# vusb.net
KiCad netlist of a schematic drawn in EAGLE
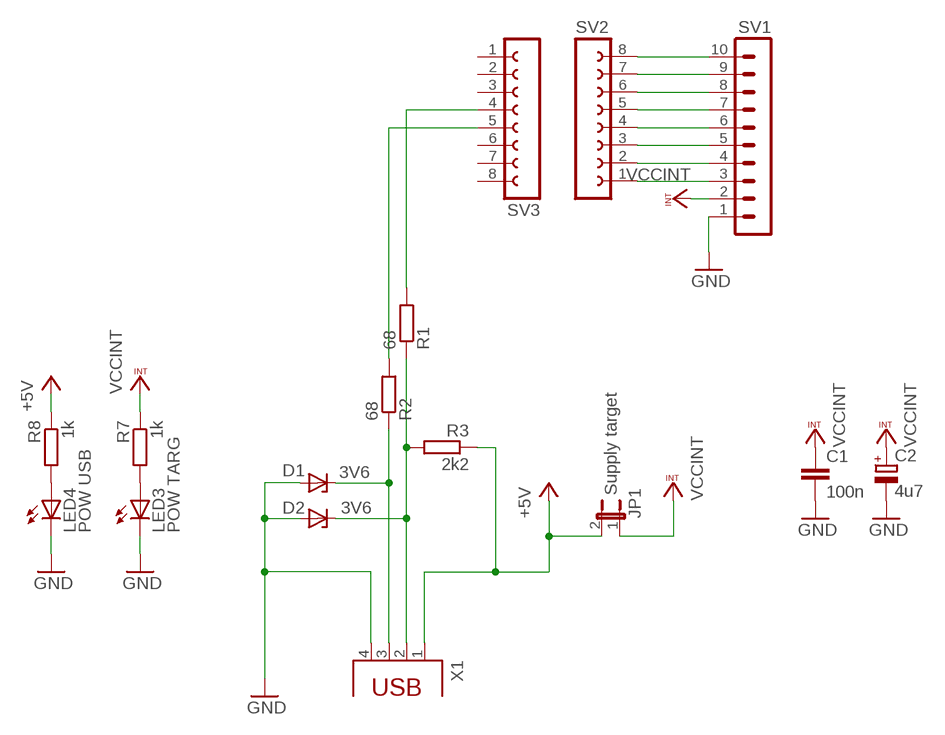
[diagram p0: schematic, sheet 1]

(export (version "E")
  (design (tool "Eeschema 10.0.6"))
  (components
    (comp (ref "C1")
      (value "100n")
      (footprint "eagle-import:C025-024X044")
      (libsource (lib "eagle-import") (part "C-EU025-024X044"))
    )
    (comp (ref "C2")
      (value "4u7")
      (footprint "eagle-import:TT2D5")
      (libsource (lib "eagle-import") (part "CPOL-EUTT2D5"))
    )
    (comp (ref "D1")
      (value "3V6")
      (footprint "eagle-import:DO34Z7")
      (libsource (lib "eagle-import") (part "ZENER-DIODEDO34-7"))
    )
    (comp (ref "D2")
      (value "3V6")
      (footprint "eagle-import:ZDIO-5")
      (libsource (lib "eagle-import") (part "ZENER-DIODEZD-5"))
    )
    (comp (ref "JP1")
      (value "Supply target")
      (footprint "eagle-import:JP1")
      (libsource (lib "eagle-import") (part "JP1E"))
    )
    (comp (ref "LED3")
      (value "POW TARG")
      (footprint "eagle-import:LED3MM")
      (libsource (lib "eagle-import") (part "LED3MM"))
    )
    (comp (ref "LED4")
      (value "POW USB")
      (footprint "eagle-import:LED3MM")
      (libsource (lib "eagle-import") (part "LED3MM"))
    )
    (comp (ref "R1")
      (value "68")
      (footprint "eagle-import:0207_10")
      (libsource (lib "eagle-import") (part "R-EU_0207/10"))
    )
    (comp (ref "R2")
      (value "68")
      (footprint "eagle-import:0207_10")
      (libsource (lib "eagle-import") (part "R-EU_0207/10"))
    )
    (comp (ref "R3")
      (value "2k2")
      (footprint "eagle-import:0204V")
      (libsource (lib "eagle-import") (part "R-EU_0204/2V"))
    )
    (comp (ref "R7")
      (value "1k")
      (footprint "eagle-import:0207_10")
      (libsource (lib "eagle-import") (part "R-EU_0207/10"))
    )
    (comp (ref "R8")
      (value "1k")
      (footprint "eagle-import:0207_10")
      (libsource (lib "eagle-import") (part "R-EU_0207/10"))
    )
    (comp (ref "SV1")
      (value "MA10-1W")
      (footprint "eagle-import:MA10-1W")
      (libsource (lib "eagle-import") (part "MA10-1W"))
    )
    (comp (ref "SV2")
      (value "FE08-1")
      (footprint "eagle-import:FE08")
      (libsource (lib "eagle-import") (part "FE08-1"))
    )
    (comp (ref "SV3")
      (value "FE08-1")
      (footprint "eagle-import:FE08")
      (libsource (lib "eagle-import") (part "FE08-1"))
    )
    (comp (ref "X1")
      (value "PN61729")
      (footprint "eagle-import:PN61729")
      (libsource (lib "eagle-import") (part "PN61729"))
    )
  )
  (nets
    (net (code "1") (name "+5V") (class "Default")
      (node (ref "JP1") (pin "2") (pinfunction "2_2") (pintype "passive"))
      (node (ref "R3") (pin "1") (pinfunction "1_1") (pintype "passive"))
      (node (ref "R8") (pin "1") (pinfunction "1_1") (pintype "passive"))
      (node (ref "X1") (pin "1") (pinfunction "1_1") (pintype "passive"))
    )
    (net (code "2") (name "GND") (class "Default")
      (node (ref "C1") (pin "2") (pinfunction "2_2") (pintype "passive"))
      (node (ref "C2") (pin "-") (pinfunction "-_-") (pintype "passive"))
      (node (ref "D1") (pin "A") (pinfunction "A_A") (pintype "passive"))
      (node (ref "D2") (pin "A") (pinfunction "A_A") (pintype "passive"))
      (node (ref "LED3") (pin "K") (pinfunction "C_K") (pintype "passive"))
      (node (ref "LED4") (pin "K") (pinfunction "C_K") (pintype "passive"))
      (node (ref "SV1") (pin "1") (pinfunction "1_1") (pintype "passive"))
      (node (ref "X1") (pin "4") (pinfunction "4_4") (pintype "passive"))
    )
    (net (code "3") (name "Net-(D1-PadC)") (class "Default")
      (node (ref "D1") (pin "C") (pinfunction "C_C") (pintype "passive"))
      (node (ref "R2") (pin "1") (pinfunction "1_1") (pintype "passive"))
      (node (ref "X1") (pin "3") (pinfunction "3_3") (pintype "passive"))
    )
    (net (code "4") (name "Net-(D2-PadC)") (class "Default")
      (node (ref "D2") (pin "C") (pinfunction "C_C") (pintype "passive"))
      (node (ref "R1") (pin "1") (pinfunction "1_1") (pintype "passive"))
      (node (ref "R3") (pin "2") (pinfunction "2_2") (pintype "passive"))
      (node (ref "X1") (pin "2") (pinfunction "2_2") (pintype "passive"))
    )
    (net (code "5") (name "Net-(LED3-PadA)") (class "Default")
      (node (ref "LED3") (pin "A") (pinfunction "A_A") (pintype "passive"))
      (node (ref "R7") (pin "2") (pinfunction "2_2") (pintype "passive"))
    )
    (net (code "6") (name "Net-(LED4-PadA)") (class "Default")
      (node (ref "LED4") (pin "A") (pinfunction "A_A") (pintype "passive"))
      (node (ref "R8") (pin "2") (pinfunction "2_2") (pintype "passive"))
    )
    (net (code "7") (name "Net-(R1-Pad2)") (class "Default")
      (node (ref "R1") (pin "2") (pinfunction "2_2") (pintype "passive"))
      (node (ref "SV3") (pin "4") (pinfunction "4_4") (pintype "passive"))
    )
    (net (code "8") (name "Net-(R2-Pad2)") (class "Default")
      (node (ref "R2") (pin "2") (pinfunction "2_2") (pintype "passive"))
      (node (ref "SV3") (pin "5") (pinfunction "5_5") (pintype "passive"))
    )
    (net (code "9") (name "Net-(SV1-Pad3)") (class "Default")
      (node (ref "SV1") (pin "3") (pinfunction "3_3") (pintype "passive"))
      (node (ref "SV2") (pin "1") (pinfunction "1_1") (pintype "passive"))
    )
    (net (code "10") (name "Net-(SV1-Pad4)") (class "Default")
      (node (ref "SV1") (pin "4") (pinfunction "4_4") (pintype "passive"))
      (node (ref "SV2") (pin "2") (pinfunction "2_2") (pintype "passive"))
    )
    (net (code "11") (name "Net-(SV1-Pad5)") (class "Default")
      (node (ref "SV1") (pin "5") (pinfunction "5_5") (pintype "passive"))
      (node (ref "SV2") (pin "3") (pinfunction "3_3") (pintype "passive"))
    )
    (net (code "12") (name "Net-(SV1-Pad6)") (class "Default")
      (node (ref "SV1") (pin "6") (pinfunction "6_6") (pintype "passive"))
      (node (ref "SV2") (pin "4") (pinfunction "4_4") (pintype "passive"))
    )
    (net (code "13") (name "Net-(SV1-Pad7)") (class "Default")
      (node (ref "SV1") (pin "7") (pinfunction "7_7") (pintype "passive"))
      (node (ref "SV2") (pin "5") (pinfunction "5_5") (pintype "passive"))
    )
    (net (code "14") (name "Net-(SV1-Pad8)") (class "Default")
      (node (ref "SV1") (pin "8") (pinfunction "8_8") (pintype "passive"))
      (node (ref "SV2") (pin "6") (pinfunction "6_6") (pintype "passive"))
    )
    (net (code "15") (name "Net-(SV1-Pad9)") (class "Default")
      (node (ref "SV1") (pin "9") (pinfunction "9_9") (pintype "passive"))
      (node (ref "SV2") (pin "7") (pinfunction "7_7") (pintype "passive"))
    )
    (net (code "16") (name "Net-(SV1-Pad10)") (class "Default")
      (node (ref "SV1") (pin "10") (pinfunction "10_10") (pintype "passive"))
      (node (ref "SV2") (pin "8") (pinfunction "8_8") (pintype "passive"))
    )
    (net (code "17") (name "VCCINT") (class "Default")
      (node (ref "C1") (pin "1") (pinfunction "1_1") (pintype "passive"))
      (node (ref "C2") (pin "+") (pinfunction "+_+") (pintype "passive"))
      (node (ref "JP1") (pin "1") (pinfunction "1_1") (pintype "passive"))
      (node (ref "R7") (pin "1") (pinfunction "1_1") (pintype "passive"))
      (node (ref "SV1") (pin "2") (pinfunction "2_2") (pintype "passive"))
    )
    (net (code "18") (name "unconnected-(SV3-Pad1)") (class "Default")
      (node (ref "SV3") (pin "1") (pinfunction "1_1") (pintype "passive"))
    )
    (net (code "19") (name "unconnected-(SV3-Pad2)") (class "Default")
      (node (ref "SV3") (pin "2") (pinfunction "2_2") (pintype "passive"))
    )
    (net (code "20") (name "unconnected-(SV3-Pad3)") (class "Default")
      (node (ref "SV3") (pin "3") (pinfunction "3_3") (pintype "passive"))
    )
    (net (code "21") (name "unconnected-(SV3-Pad6)") (class "Default")
      (node (ref "SV3") (pin "6") (pinfunction "6_6") (pintype "passive"))
    )
    (net (code "22") (name "unconnected-(SV3-Pad7)") (class "Default")
      (node (ref "SV3") (pin "7") (pinfunction "7_7") (pintype "passive"))
    )
    (net (code "23") (name "unconnected-(SV3-Pad8)") (class "Default")
      (node (ref "SV3") (pin "8") (pinfunction "8_8") (pintype "passive"))
    )
  )
)
